# 07_SENSOR.net
KiCad netlist of a schematic drawn in Altium Designer
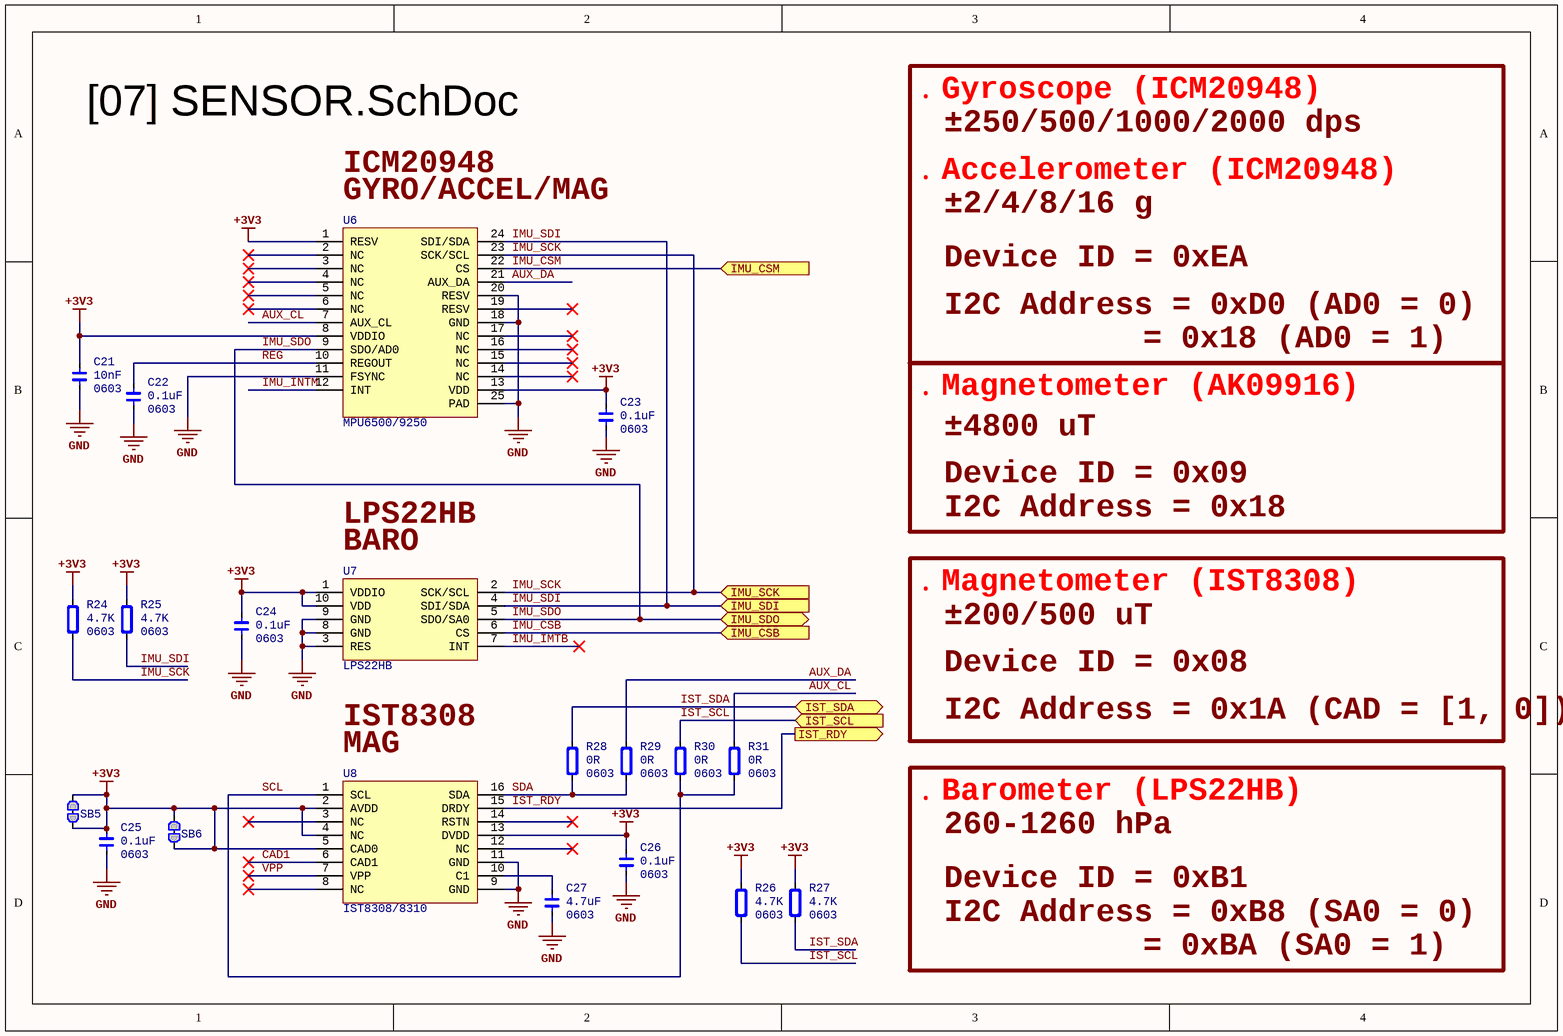
[diagram p0: [07] SENSOR.SchDoc]

(export (version "E")
  (design (tool "Eeschema 10.0.6"))
  (components
    (comp (ref "C21")
      (value "10nF")
      (footprint "PCB_PassiveCap:CAP_0603")
      (description "Capacitor")
      (fields (field (name "TYPE") "0603"))
      (libsource (lib "SCH_Passive") (part "Cap_0603"))
    )
    (comp (ref "C22")
      (value "0.1uF")
      (footprint "PCB_PassiveCap:CAP_0603")
      (description "Capacitor")
      (fields (field (name "TYPE") "0603"))
      (libsource (lib "SCH_Passive") (part "Cap_0603"))
    )
    (comp (ref "C23")
      (value "0.1uF")
      (footprint "PCB_PassiveCap:CAP_0603")
      (description "Capacitor")
      (fields (field (name "TYPE") "0603"))
      (libsource (lib "SCH_Passive") (part "Cap_0603"))
    )
    (comp (ref "C24")
      (value "0.1uF")
      (footprint "PCB_PassiveCap:CAP_0603")
      (description "Capacitor")
      (fields (field (name "TYPE") "0603"))
      (libsource (lib "SCH_Passive") (part "Cap_0603"))
    )
    (comp (ref "C25")
      (value "0.1uF")
      (footprint "PCB_PassiveCap:CAP_0603")
      (description "Capacitor")
      (fields (field (name "TYPE") "0603"))
      (libsource (lib "SCH_Passive") (part "Cap_0603"))
    )
    (comp (ref "C26")
      (value "0.1uF")
      (footprint "PCB_PassiveCap:CAP_0603")
      (description "Capacitor")
      (fields (field (name "TYPE") "0603"))
      (libsource (lib "SCH_Passive") (part "Cap_0603"))
    )
    (comp (ref "C27")
      (value "4.7uF")
      (footprint "PCB_PassiveCap:CAP_0603")
      (description "Capacitor")
      (fields (field (name "TYPE") "0603"))
      (libsource (lib "SCH_Passive") (part "Cap_0603"))
    )
    (comp (ref "R24")
      (value "4.7K")
      (footprint "PCB_PassiveRes:RES_0603")
      (description "Resistor")
      (fields (field (name "TYPE") "0603"))
      (libsource (lib "SCH_Passive") (part "Res_0603"))
    )
    (comp (ref "R25")
      (value "4.7K")
      (footprint "PCB_PassiveRes:RES_0603")
      (description "Resistor")
      (fields (field (name "TYPE") "0603"))
      (libsource (lib "SCH_Passive") (part "Res_0603"))
    )
    (comp (ref "R26")
      (value "4.7K")
      (footprint "PCB_PassiveRes:RES_0603")
      (description "Resistor")
      (fields (field (name "TYPE") "0603"))
      (libsource (lib "SCH_Passive") (part "Res_0603"))
    )
    (comp (ref "R27")
      (value "4.7K")
      (footprint "PCB_PassiveRes:RES_0603")
      (description "Resistor")
      (fields (field (name "TYPE") "0603"))
      (libsource (lib "SCH_Passive") (part "Res_0603"))
    )
    (comp (ref "R28")
      (value "0R")
      (footprint "PCB_PassiveRes:RES_0603")
      (description "Resistor")
      (fields (field (name "TYPE") "0603"))
      (libsource (lib "SCH_Passive") (part "Res_0603"))
    )
    (comp (ref "R29")
      (value "0R")
      (footprint "PCB_PassiveRes:RES_0603")
      (description "Resistor")
      (fields (field (name "TYPE") "0603"))
      (libsource (lib "SCH_Passive") (part "Res_0603"))
    )
    (comp (ref "R30")
      (value "0R")
      (footprint "PCB_PassiveRes:RES_0603")
      (description "Resistor")
      (fields (field (name "TYPE") "0603"))
      (libsource (lib "SCH_Passive") (part "Res_0603"))
    )
    (comp (ref "R31")
      (value "0R")
      (footprint "PCB_PassiveRes:RES_0603")
      (description "Resistor")
      (fields (field (name "TYPE") "0603"))
      (libsource (lib "SCH_Passive") (part "Res_0603"))
    )
    (comp (ref "SB5")
      (value "Solderbridge")
      (footprint "PCB_Mechanical:Solderbridge_Shorted")
      (description "Shorted Solderbridge")
      (libsource (lib "SCH_Mechanical") (part "Shorted Solderbridge"))
    )
    (comp (ref "SB6")
      (value "Solderbridge")
      (footprint "PCB_Mechanical:Solderbridge_Shorted")
      (description "Shorted Solderbridge")
      (libsource (lib "SCH_Mechanical") (part "Shorted Solderbridge"))
    )
    (comp (ref "U6")
      (value "MPU6500/9250")
      (footprint "PCB_IntegratedCircuit:QFN_P0.4_24")
      (description "Sensor Motion")
      (libsource (lib "SCH_IntegratedCircuit") (part "MPU925x"))
    )
    (comp (ref "U7")
      (value "LPS22HB")
      (footprint "PCB_IntegratedCircuit:HCLGA-2x2_10")
      (description "Sensor Pressure")
      (libsource (lib "SCH_IntegratedCircuit") (part "LPS22HB"))
    )
    (comp (ref "U8")
      (value "IST8308/8310")
      (footprint "PCB_IntegratedCircuit:QFN_P0.5_16")
      (description "Sensor Magnetometer")
      (libsource (lib "SCH_IntegratedCircuit") (part "IST8310"))
    )
  )
  (nets
    (net (code "1") (name "+3V3") (class "Default")
      (node (ref "C21") (pin "2") (pinfunction "2_2") (pintype "passive"))
      (node (ref "C23") (pin "2") (pinfunction "2_2") (pintype "passive"))
      (node (ref "C24") (pin "2") (pinfunction "2_2") (pintype "passive"))
      (node (ref "C25") (pin "2") (pinfunction "2_2") (pintype "passive"))
      (node (ref "C26") (pin "2") (pinfunction "2_2") (pintype "passive"))
      (node (ref "R24") (pin "2") (pinfunction "2_2") (pintype "passive"))
      (node (ref "R25") (pin "2") (pinfunction "2_2") (pintype "passive"))
      (node (ref "R26") (pin "2") (pinfunction "2_2") (pintype "passive"))
      (node (ref "R27") (pin "2") (pinfunction "2_2") (pintype "passive"))
      (node (ref "SB5") (pin "1") (pinfunction "1_1") (pintype "passive"))
      (node (ref "SB5") (pin "2") (pinfunction "2_2") (pintype "passive"))
      (node (ref "SB6") (pin "1") (pinfunction "1_1") (pintype "passive"))
      (node (ref "SB6") (pin "2") (pinfunction "2_2") (pintype "passive"))
      (node (ref "U6") (pin "1") (pinfunction "RESV_1") (pintype "passive"))
      (node (ref "U6") (pin "13") (pinfunction "VDD_13") (pintype "passive"))
      (node (ref "U6") (pin "8") (pinfunction "VDDIO_8") (pintype "passive"))
      (node (ref "U7") (pin "1") (pinfunction "VDDIO_1") (pintype "passive"))
      (node (ref "U7") (pin "10") (pinfunction "VDD_10") (pintype "passive"))
      (node (ref "U8") (pin "13") (pinfunction "DVDD_13") (pintype "passive"))
      (node (ref "U8") (pin "2") (pinfunction "AVDD_2") (pintype "passive"))
      (node (ref "U8") (pin "4") (pinfunction "NC_4") (pintype "passive"))
      (node (ref "U8") (pin "5") (pinfunction "CAD0_5") (pintype "passive"))
    )
    (net (code "2") (name "/AUX_CL") (class "Default")
      (node (ref "R31") (pin "2") (pinfunction "2_2") (pintype "passive"))
      (node (ref "U6") (pin "7") (pinfunction "AUX_CL_7") (pintype "passive"))
    )
    (net (code "3") (name "/AUX_DA") (class "Default")
      (node (ref "R29") (pin "2") (pinfunction "2_2") (pintype "passive"))
      (node (ref "U6") (pin "21") (pinfunction "AUX_DA_21") (pintype "passive"))
    )
    (net (code "4") (name "/CAD1") (class "Default")
      (node (ref "U8") (pin "6") (pinfunction "CAD1_6") (pintype "passive+no_connect"))
    )
    (net (code "5") (name "/IMU_CSB") (class "Default")
      (node (ref "U7") (pin "6") (pinfunction "CS_6") (pintype "passive"))
    )
    (net (code "6") (name "/IMU_CSM") (class "Default")
      (node (ref "U6") (pin "22") (pinfunction "CS_22") (pintype "passive"))
    )
    (net (code "7") (name "/IMU_IMTB") (class "Default")
      (node (ref "U7") (pin "7") (pinfunction "INT_7") (pintype "passive+no_connect"))
    )
    (net (code "8") (name "/IMU_INTM") (class "Default")
      (node (ref "U6") (pin "12") (pinfunction "INT_12") (pintype "passive"))
    )
    (net (code "9") (name "/IMU_SCK") (class "Default")
      (node (ref "R24") (pin "1") (pinfunction "1_1") (pintype "passive"))
      (node (ref "U6") (pin "23") (pinfunction "SCK/SCL_23") (pintype "passive"))
      (node (ref "U7") (pin "2") (pinfunction "SCK/SCL_2") (pintype "passive"))
    )
    (net (code "10") (name "/IMU_SDI") (class "Default")
      (node (ref "R25") (pin "1") (pinfunction "1_1") (pintype "passive"))
      (node (ref "U6") (pin "24") (pinfunction "SDI/SDA_24") (pintype "passive"))
      (node (ref "U7") (pin "4") (pinfunction "SDI/SDA_4") (pintype "passive"))
    )
    (net (code "11") (name "/IMU_SDO") (class "Default")
      (node (ref "U6") (pin "9") (pinfunction "SDO/AD0_9") (pintype "passive"))
      (node (ref "U7") (pin "5") (pinfunction "SDO/SA0_5") (pintype "passive"))
    )
    (net (code "12") (name "/IST_RDY") (class "Default")
      (node (ref "U8") (pin "15") (pinfunction "DRDY_15") (pintype "passive"))
    )
    (net (code "13") (name "/IST_SCL") (class "Default")
      (node (ref "R26") (pin "1") (pinfunction "1_1") (pintype "passive"))
      (node (ref "R30") (pin "2") (pinfunction "2_2") (pintype "passive"))
    )
    (net (code "14") (name "/IST_SDA") (class "Default")
      (node (ref "R27") (pin "1") (pinfunction "1_1") (pintype "passive"))
      (node (ref "R28") (pin "2") (pinfunction "2_2") (pintype "passive"))
    )
    (net (code "15") (name "/REG") (class "Default")
      (node (ref "C22") (pin "2") (pinfunction "2_2") (pintype "passive"))
      (node (ref "U6") (pin "10") (pinfunction "REGOUT_10") (pintype "passive"))
    )
    (net (code "16") (name "/SCL") (class "Default")
      (node (ref "R30") (pin "1") (pinfunction "1_1") (pintype "passive"))
      (node (ref "R31") (pin "1") (pinfunction "1_1") (pintype "passive"))
      (node (ref "U8") (pin "1") (pinfunction "SCL_1") (pintype "passive"))
    )
    (net (code "17") (name "/SDA") (class "Default")
      (node (ref "R28") (pin "1") (pinfunction "1_1") (pintype "passive"))
      (node (ref "R29") (pin "1") (pinfunction "1_1") (pintype "passive"))
      (node (ref "U8") (pin "16") (pinfunction "SDA_16") (pintype "passive"))
    )
    (net (code "18") (name "/VPP") (class "Default")
      (node (ref "U8") (pin "7") (pinfunction "VPP_7") (pintype "passive+no_connect"))
    )
    (net (code "19") (name "GND") (class "Default")
      (node (ref "C21") (pin "1") (pinfunction "1_1") (pintype "passive"))
      (node (ref "C22") (pin "1") (pinfunction "1_1") (pintype "passive"))
      (node (ref "C23") (pin "1") (pinfunction "1_1") (pintype "passive"))
      (node (ref "C24") (pin "1") (pinfunction "1_1") (pintype "passive"))
      (node (ref "C25") (pin "1") (pinfunction "1_1") (pintype "passive"))
      (node (ref "C26") (pin "1") (pinfunction "1_1") (pintype "passive"))
      (node (ref "C27") (pin "1") (pinfunction "1_1") (pintype "passive"))
      (node (ref "U6") (pin "11") (pinfunction "FSYNC_11") (pintype "passive"))
      (node (ref "U6") (pin "18") (pinfunction "GND_18") (pintype "passive"))
      (node (ref "U6") (pin "20") (pinfunction "RESV_20") (pintype "passive"))
      (node (ref "U6") (pin "25") (pinfunction "PAD_25") (pintype "passive"))
      (node (ref "U7") (pin "3") (pinfunction "RES_3") (pintype "passive"))
      (node (ref "U7") (pin "8") (pinfunction "GND_8") (pintype "passive"))
      (node (ref "U7") (pin "9") (pinfunction "GND_9") (pintype "passive"))
      (node (ref "U8") (pin "11") (pinfunction "GND_11") (pintype "passive"))
      (node (ref "U8") (pin "9") (pinfunction "GND_9") (pintype "passive"))
    )
    (net (code "20") (name "Net-(U8-C1)") (class "Default")
      (node (ref "C27") (pin "2") (pinfunction "2_2") (pintype "passive"))
      (node (ref "U8") (pin "10") (pinfunction "C1_10") (pintype "passive"))
    )
    (net (code "21") (name "unconnected-(U6-NC-Pad2)") (class "Default")
      (node (ref "U6") (pin "2") (pinfunction "NC_2") (pintype "passive+no_connect"))
    )
    (net (code "22") (name "unconnected-(U6-NC-Pad3)") (class "Default")
      (node (ref "U6") (pin "3") (pinfunction "NC_3") (pintype "passive+no_connect"))
    )
    (net (code "23") (name "unconnected-(U6-NC-Pad4)") (class "Default")
      (node (ref "U6") (pin "4") (pinfunction "NC_4") (pintype "passive+no_connect"))
    )
    (net (code "24") (name "unconnected-(U6-NC-Pad5)") (class "Default")
      (node (ref "U6") (pin "5") (pinfunction "NC_5") (pintype "passive+no_connect"))
    )
    (net (code "25") (name "unconnected-(U6-NC-Pad6)") (class "Default")
      (node (ref "U6") (pin "6") (pinfunction "NC_6") (pintype "passive+no_connect"))
    )
    (net (code "26") (name "unconnected-(U6-NC-Pad14)") (class "Default")
      (node (ref "U6") (pin "14") (pinfunction "NC_14") (pintype "passive+no_connect"))
    )
    (net (code "27") (name "unconnected-(U6-NC-Pad15)") (class "Default")
      (node (ref "U6") (pin "15") (pinfunction "NC_15") (pintype "passive+no_connect"))
    )
    (net (code "28") (name "unconnected-(U6-NC-Pad16)") (class "Default")
      (node (ref "U6") (pin "16") (pinfunction "NC_16") (pintype "passive+no_connect"))
    )
    (net (code "29") (name "unconnected-(U6-NC-Pad17)") (class "Default")
      (node (ref "U6") (pin "17") (pinfunction "NC_17") (pintype "passive+no_connect"))
    )
    (net (code "30") (name "unconnected-(U6-RESV-Pad19)") (class "Default")
      (node (ref "U6") (pin "19") (pinfunction "RESV_19") (pintype "passive+no_connect"))
    )
    (net (code "31") (name "unconnected-(U8-NC-Pad3)") (class "Default")
      (node (ref "U8") (pin "3") (pinfunction "NC_3") (pintype "passive+no_connect"))
    )
    (net (code "32") (name "unconnected-(U8-NC-Pad8)") (class "Default")
      (node (ref "U8") (pin "8") (pinfunction "NC_8") (pintype "passive+no_connect"))
    )
    (net (code "33") (name "unconnected-(U8-NC-Pad12)") (class "Default")
      (node (ref "U8") (pin "12") (pinfunction "NC_12") (pintype "passive+no_connect"))
    )
    (net (code "34") (name "unconnected-(U8-RSTN-Pad14)") (class "Default")
      (node (ref "U8") (pin "14") (pinfunction "RSTN_14") (pintype "passive+no_connect"))
    )
  )
)
